# EspWifiMk2.net
KiCad netlist of a schematic drawn in EAGLE
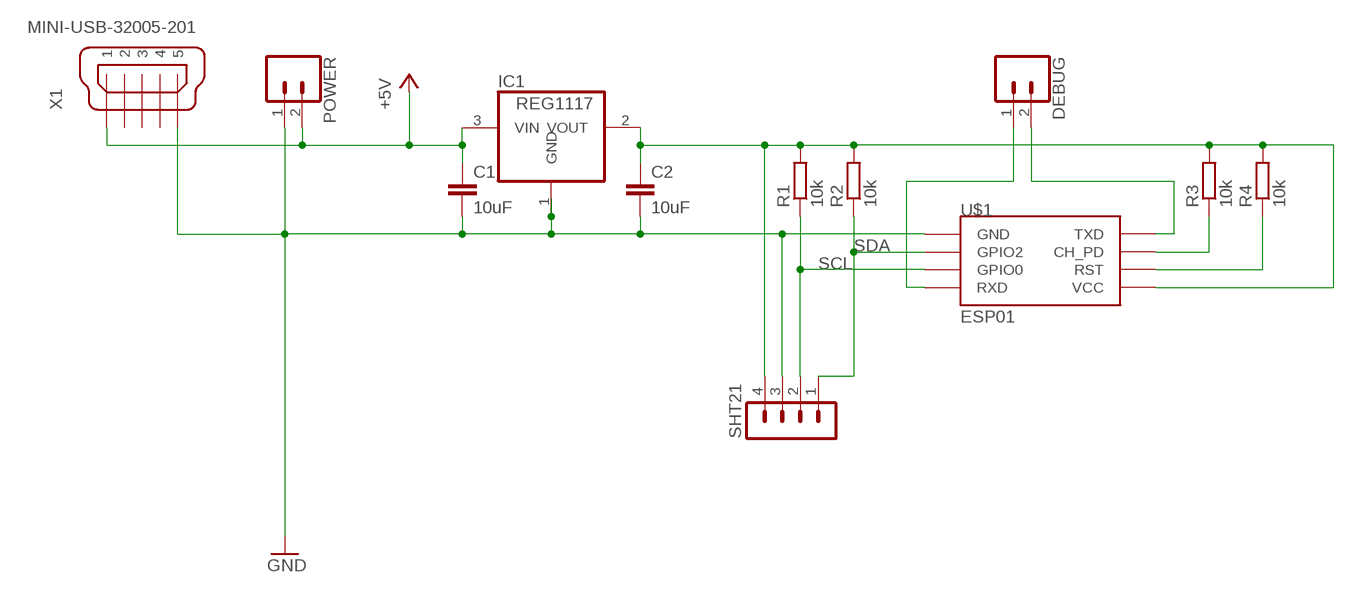
[diagram p0: schematic, sheet 1]

(export (version "E")
  (design (tool "Eeschema 10.0.6"))
  (components
    (comp (ref "C1")
      (value "10uF")
      (footprint "eagle-import:C1206")
      (libsource (lib "eagle-import") (part "C-EUC1206"))
    )
    (comp (ref "C2")
      (value "10uF")
      (footprint "eagle-import:C1206")
      (libsource (lib "eagle-import") (part "C-EUC1206"))
    )
    (comp (ref "DEBUG")
      (value "CONN_02")
      (footprint "eagle-import:1X02")
      (libsource (lib "eagle-import") (part "CONN_02"))
    )
    (comp (ref "IC1")
      (value "REG1117")
      (footprint "eagle-import:SOT223")
      (libsource (lib "eagle-import") (part "REG1117"))
    )
    (comp (ref "POWER")
      (value "CONN_02")
      (footprint "eagle-import:1X02")
      (libsource (lib "eagle-import") (part "CONN_02"))
    )
    (comp (ref "R1")
      (value "10k")
      (footprint "eagle-import:M1206")
      (libsource (lib "eagle-import") (part "R-EU_M1206"))
    )
    (comp (ref "R2")
      (value "10k")
      (footprint "eagle-import:M1206")
      (libsource (lib "eagle-import") (part "R-EU_M1206"))
    )
    (comp (ref "R3")
      (value "10k")
      (footprint "eagle-import:M1206")
      (libsource (lib "eagle-import") (part "R-EU_M1206"))
    )
    (comp (ref "R4")
      (value "10k")
      (footprint "eagle-import:M1206")
      (libsource (lib "eagle-import") (part "R-EU_M1206"))
    )
    (comp (ref "SHT21")
      (value "MA04-1")
      (footprint "eagle-import:MA04-1")
      (libsource (lib "eagle-import") (part "MA04-1"))
    )
    (comp (ref "U$1")
      (value "ESP01")
      (footprint "eagle-import:ESP01")
      (libsource (lib "eagle-import") (part "ESP01"))
    )
    (comp (ref "X1")
      (value "MINI-USB-32005-201")
      (footprint "eagle-import:32005-201")
      (libsource (lib "eagle-import") (part "MINI-USB-32005-201"))
    )
  )
  (nets
    (net (code "1") (name "+5V") (class "Default")
      (node (ref "C1") (pin "1") (pinfunction "1_1") (pintype "passive"))
      (node (ref "IC1") (pin "3") (pinfunction "VIN_3") (pintype "input"))
      (node (ref "POWER") (pin "2") (pinfunction "2_2") (pintype "passive"))
      (node (ref "X1") (pin "1") (pinfunction "1_1") (pintype "passive"))
    )
    (net (code "2") (name "/SCL") (class "Default")
      (node (ref "R1") (pin "1") (pinfunction "1_1") (pintype "passive"))
      (node (ref "SHT21") (pin "2") (pinfunction "2_2") (pintype "passive"))
      (node (ref "U$1") (pin "GPIO0") (pinfunction "GPIO0_GPIO0") (pintype "bidirectional"))
    )
    (net (code "3") (name "/SDA") (class "Default")
      (node (ref "R2") (pin "1") (pinfunction "1_1") (pintype "passive"))
      (node (ref "SHT21") (pin "1") (pinfunction "1_1") (pintype "passive"))
      (node (ref "U$1") (pin "GPIO2") (pinfunction "GPIO2_GPIO2") (pintype "bidirectional"))
    )
    (net (code "4") (name "GND") (class "Default")
      (node (ref "C1") (pin "2") (pinfunction "2_2") (pintype "passive"))
      (node (ref "C2") (pin "2") (pinfunction "2_2") (pintype "passive"))
      (node (ref "IC1") (pin "1") (pinfunction "GND_1") (pintype "power_in"))
      (node (ref "POWER") (pin "1") (pinfunction "1_1") (pintype "passive"))
      (node (ref "SHT21") (pin "3") (pinfunction "3_3") (pintype "passive"))
      (node (ref "U$1") (pin "GND") (pinfunction "GND_GND") (pintype "bidirectional"))
      (node (ref "X1") (pin "5") (pinfunction "5_5") (pintype "passive"))
    )
    (net (code "5") (name "Net-(IC1-VOUT)") (class "Default")
      (node (ref "C2") (pin "1") (pinfunction "1_1") (pintype "passive"))
      (node (ref "IC1") (pin "2") (pinfunction "VOUT_2") (pintype "output"))
      (node (ref "R1") (pin "2") (pinfunction "2_2") (pintype "passive"))
      (node (ref "R2") (pin "2") (pinfunction "2_2") (pintype "passive"))
      (node (ref "R3") (pin "2") (pinfunction "2_2") (pintype "passive"))
      (node (ref "R4") (pin "2") (pinfunction "2_2") (pintype "passive"))
      (node (ref "SHT21") (pin "4") (pinfunction "4_4") (pintype "passive"))
      (node (ref "U$1") (pin "VCC") (pinfunction "VCC_VCC") (pintype "bidirectional"))
    )
    (net (code "6") (name "Net-(R3-Pad1)") (class "Default")
      (node (ref "R3") (pin "1") (pinfunction "1_1") (pintype "passive"))
      (node (ref "U$1") (pin "CH_PD") (pinfunction "CH_PD_CH_PD") (pintype "bidirectional"))
    )
    (net (code "7") (name "Net-(R4-Pad1)") (class "Default")
      (node (ref "R4") (pin "1") (pinfunction "1_1") (pintype "passive"))
      (node (ref "U$1") (pin "RST") (pinfunction "RST_RST") (pintype "bidirectional"))
    )
    (net (code "8") (name "Net-(U$1-RXD)") (class "Default")
      (node (ref "DEBUG") (pin "1") (pinfunction "1_1") (pintype "passive"))
      (node (ref "U$1") (pin "RX") (pinfunction "RXD_RX") (pintype "bidirectional"))
    )
    (net (code "9") (name "Net-(U$1-TXD)") (class "Default")
      (node (ref "DEBUG") (pin "2") (pinfunction "2_2") (pintype "passive"))
      (node (ref "U$1") (pin "TX") (pinfunction "TXD_TX") (pintype "bidirectional"))
    )
    (net (code "10") (name "unconnected-(X1-Pad2)") (class "Default")
      (node (ref "X1") (pin "2") (pinfunction "2_2") (pintype "passive"))
    )
    (net (code "11") (name "unconnected-(X1-Pad3)") (class "Default")
      (node (ref "X1") (pin "3") (pinfunction "3_3") (pintype "passive"))
    )
    (net (code "12") (name "unconnected-(X1-Pad4)") (class "Default")
      (node (ref "X1") (pin "4") (pinfunction "4_4") (pintype "passive"))
    )
  )
)
